# Sheet1.net
KiCad netlist of a schematic drawn in Altium Designer
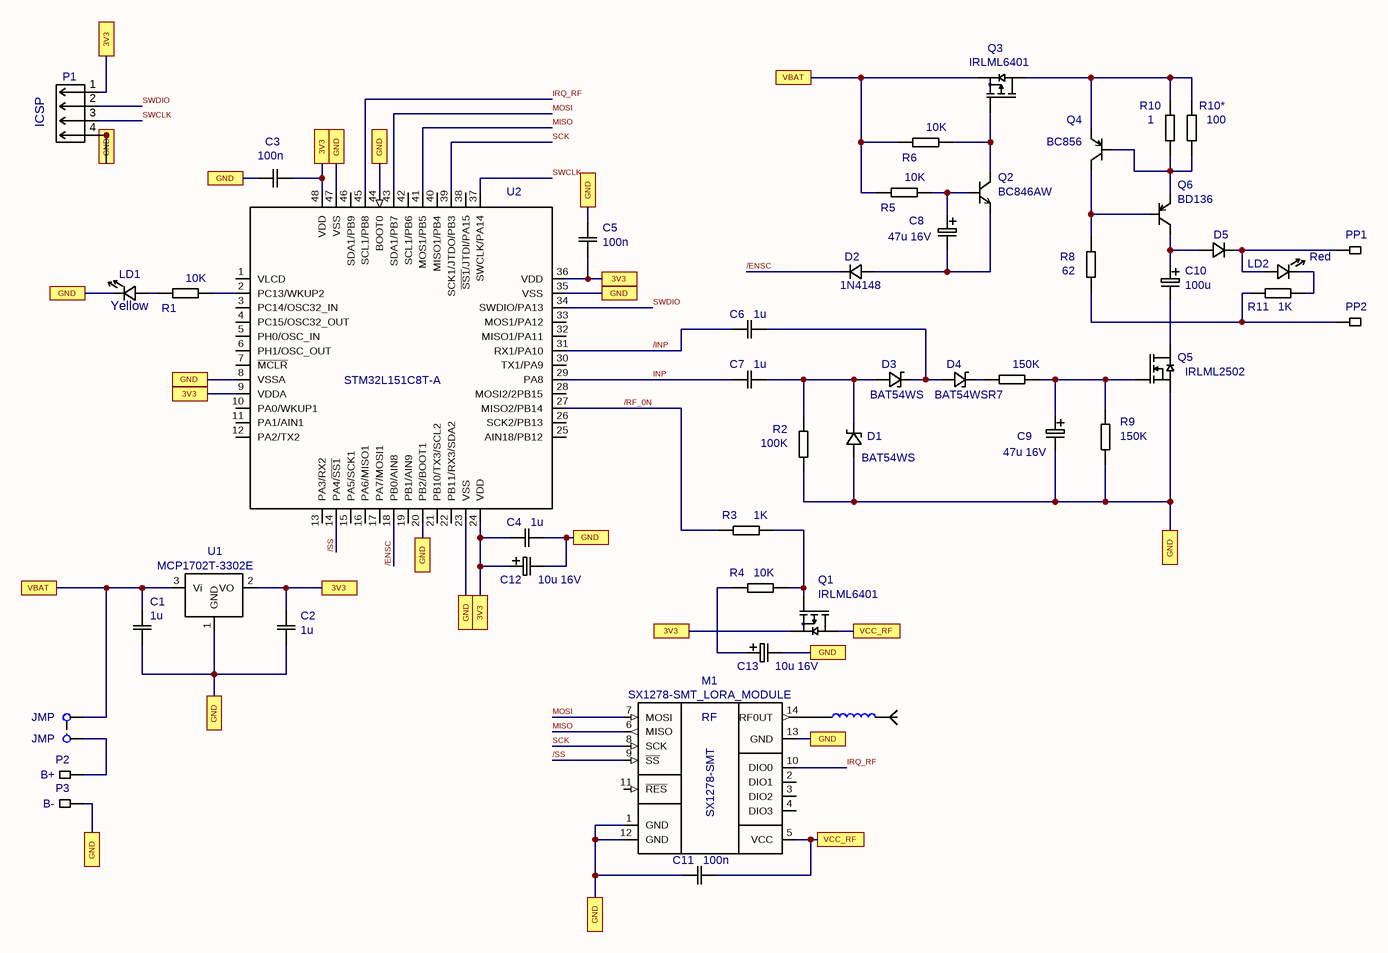
[diagram p0: Sheet1.SCHDOC]

(export (version "E")
  (design (tool "Eeschema 10.0.6"))
  (components
    (comp (ref "C1")
      (value "1u")
      (footprint "C0805")
      (description "CAP_SMD_0805")
      (libsource (lib "*") (part "CAP_SMD_0805"))
    )
    (comp (ref "C2")
      (value "1u")
      (footprint "C0805")
      (description "CAP_SMD_0805")
      (libsource (lib "*") (part "CAP_SMD_0805"))
    )
    (comp (ref "C3")
      (value "100n")
      (footprint "C0805")
      (description "CAP_SMD_0805")
      (libsource (lib "") (part "CAP_SMD_0805_1"))
    )
    (comp (ref "C4")
      (value "1u")
      (footprint "C0805")
      (description "CAP_SMD_0805")
      (libsource (lib "") (part "CAP_SMD_0805_1"))
    )
    (comp (ref "C5")
      (value "100n")
      (footprint "C0805")
      (description "CAP_SMD_0805")
      (libsource (lib "*") (part "CAP_SMD_0805"))
    )
    (comp (ref "C6")
      (value "1u")
      (footprint "C0805")
      (description "CAP_SMD_0805")
      (libsource (lib "") (part "CAP_SMD_0805_1"))
    )
    (comp (ref "C7")
      (value "1u")
      (footprint "C0805")
      (description "CAP_SMD_0805")
      (libsource (lib "") (part "CAP_SMD_0805_2"))
    )
    (comp (ref "C8")
      (value "47u 16V")
      (footprint "ECAP-SD-D5L11")
      (description "ECAP-RD-D5L11")
      (libsource (lib "*") (part "ECAP-RD-D5L11"))
    )
    (comp (ref "C9")
      (value "47u 16V")
      (footprint "ECAP-SD-D5L11")
      (description "ECAP-RD-D5L11")
      (libsource (lib "*") (part "ECAP-RD-D5L11"))
    )
    (comp (ref "C10")
      (value "100u")
      (footprint "ECAP-SD-D6.3L11")
      (description "ECAP-RD-D6.3L11")
      (libsource (lib "*") (part "ECAP-RD-D6.3L11"))
    )
    (comp (ref "C11")
      (value "100n")
      (footprint "C0805")
      (description "CAP_SMD_0805")
      (libsource (lib "") (part "CAP_SMD_0805_2"))
    )
    (comp (ref "C12")
      (value "10u 16V")
      (footprint "ECAP-SD-D5L11")
      (description "ECAP-RD-D5L11")
      (libsource (lib "*") (part "ECAP-RD-D5L11"))
    )
    (comp (ref "C13")
      (value "10u 16V")
      (footprint "ECAP-SD-D5L11")
      (description "ECAP-RD-D5L11")
      (libsource (lib "*") (part "ECAP-RD-D5L11"))
    )
    (comp (ref "D1") (value "BAT54WS") (footprint "SOD323") (libsource (lib "*") (part "BAT54WS")))
    (comp (ref "D2") (value "1N4148") (footprint "SOD80") (libsource (lib "*") (part "1N4148")))
    (comp (ref "D3") (value "BAT54WS") (footprint "SOD323") (libsource (lib "*") (part "BAT54WS")))
    (comp (ref "D4") (value "BAT54WS") (footprint "SOD323") (libsource (lib "*") (part "BAT54WS")))
    (comp (ref "D5") (value "1N4007-A7") (footprint "SOD-123FL") (libsource (lib "*") (part "1N4007-A7")))
    (comp (ref "LD1")
      (value "Yellow")
      (footprint "LED_SMD_0805")
      (description "Yellow LED. 2.6Vf")
      (fields (field (name "Comment") "FYLS-0805BYC LED"))
      (libsource (lib "*") (part "FYLS-0805BYC LED"))
    )
    (comp (ref "LD2")
      (value "Red")
      (footprint "LED_SMD_0805")
      (description "Ultra Red. Vf-1.85V(2.2V max)")
      (fields (field (name "Comment") "FYLS-0805URC LED"))
      (libsource (lib "*") (part "FYLS-0805URC LED"))
    )
    (comp (ref "M1")
      (value "SX1278-SMT_LORA_MODULE")
      (footprint "SX1278-SMT_MODULE")
      (libsource (lib "*") (part "SX1278-SMT_LORA_MODULE"))
    )
    (comp (ref "P1")
      (value "ICSP")
      (footprint "PLS-04SMD")
      (description "PLS-04SMD")
      (libsource (lib "*") (part "PLS-04SMD"))
    )
    (comp (ref "P2")
      (value "B+")
      (footprint "PAD_RRX60Y120D0T")
      (description "PAD_RRX60Y120D0T")
      (libsource (lib "*") (part "PAD_RRX60Y120D0T"))
    )
    (comp (ref "P3")
      (value "B-")
      (footprint "PAD_RRX60Y120D0T")
      (description "PAD_RRX60Y120D0T")
      (libsource (lib "*") (part "PAD_RRX60Y120D0T"))
    )
    (comp (ref "PP1")
      (value "PAD_RRX60Y120D0T")
      (footprint "PAD_RRX60Y120D0T")
      (libsource (lib "*") (part "PAD_RRX60Y120D0T"))
    )
    (comp (ref "PP2")
      (value "PAD_RRX60Y120D0T")
      (footprint "PAD_RRX60Y120D0T")
      (libsource (lib "*") (part "PAD_RRX60Y120D0T"))
    )
    (comp (ref "PP3")
      (value "JMP")
      (footprint "PAD_RX60Y60D38A")
      (description "PAD_RX60Y60D38A")
      (libsource (lib "*") (part "PAD_RX60Y60D38A"))
    )
    (comp (ref "PP4")
      (value "JMP")
      (footprint "PAD_RX60Y60D38A")
      (description "PAD_RX60Y60D38A")
      (libsource (lib "*") (part "PAD_RX60Y60D38A"))
    )
    (comp (ref "Q1") (value "IRLML6401") (footprint "SOT23") (libsource (lib "*") (part "IRLML6401")))
    (comp (ref "Q2") (value "BC846AW") (footprint "SOT23") (libsource (lib "*") (part "BC846AW")))
    (comp (ref "Q3") (value "IRLML6401") (footprint "SOT23") (libsource (lib "") (part "IRLML6401_1")))
    (comp (ref "Q4") (value "BC856") (footprint "SOT23") (libsource (lib "*") (part "BC856")))
    (comp (ref "Q5") (value "IRLML2502") (footprint "SOT23") (libsource (lib "*") (part "IRLML2502")))
    (comp (ref "Q6") (value "BD136") (footprint "TO225 VH") (libsource (lib "*") (part "BD136")))
    (comp (ref "R1")
      (value "10K")
      (footprint "R0805")
      (description "RES_SMD_0805")
      (libsource (lib "*") (part "RES_SMD_0805"))
    )
    (comp (ref "R2")
      (value "100K")
      (footprint "R0805")
      (description "RES_SMD_0805")
      (libsource (lib "*") (part "RES_SMD_0805"))
    )
    (comp (ref "R3")
      (value "1K")
      (footprint "R0805")
      (description "RES_SMD_0805")
      (libsource (lib "*") (part "RES_SMD_0805"))
    )
    (comp (ref "R4")
      (value "10K")
      (footprint "R0805")
      (description "RES_SMD_0805")
      (libsource (lib "*") (part "RES_SMD_0805"))
    )
    (comp (ref "R5")
      (value "10K")
      (footprint "R0805")
      (description "RES_SMD_0805")
      (libsource (lib "*") (part "RES_SMD_0805"))
    )
    (comp (ref "R6")
      (value "10K")
      (footprint "R0805")
      (description "RES_SMD_0805")
      (libsource (lib "*") (part "RES_SMD_0805"))
    )
    (comp (ref "R7")
      (value "150K")
      (footprint "R0805")
      (description "RES_SMD_0805")
      (libsource (lib "*") (part "RES_SMD_0805"))
    )
    (comp (ref "R8")
      (value "62")
      (footprint "R0805")
      (description "RES_SMD_0805")
      (libsource (lib "*") (part "RES_SMD_0805"))
    )
    (comp (ref "R9")
      (value "150K")
      (footprint "R0805")
      (description "RES_SMD_0805")
      (libsource (lib "*") (part "RES_SMD_0805"))
    )
    (comp (ref "R10")
      (value "1")
      (footprint "R0805")
      (description "RES_SMD_0805")
      (libsource (lib "*") (part "RES_SMD_0805"))
    )
    (comp (ref "R10*")
      (value "100")
      (footprint "R0805")
      (description "RES_SMD_0805")
      (libsource (lib "*") (part "RES_SMD_0805"))
    )
    (comp (ref "R11")
      (value "1K")
      (footprint "R0805")
      (description "RES_SMD_0805")
      (libsource (lib "*") (part "RES_SMD_0805"))
    )
    (comp (ref "U1")
      (value "MCP1702T-3302E")
      (footprint "SOT23A")
      (libsource (lib "*") (part "MCP1702T-3302E"))
    )
    (comp (ref "U2")
      (value "STM32L151C8T-A")
      (footprint "LQFP48 7X7")
      (libsource (lib "*") (part "STM32L151C8T-A"))
    )
  )
  (nets
    (net (code "1") (name "/3V3") (class "Default")
      (node (ref "C12") (pin "1") (pintype "passive"))
      (node (ref "C2") (pin "2") (pinfunction "B_2") (pintype "passive"))
      (node (ref "C3") (pin "1") (pinfunction "A_1") (pintype "passive"))
      (node (ref "C4") (pin "2") (pinfunction "B_2") (pintype "passive"))
      (node (ref "C5") (pin "1") (pinfunction "A_1") (pintype "passive"))
      (node (ref "P1") (pin "1") (pintype "passive"))
      (node (ref "Q1") (pin "2") (pinfunction "S_2") (pintype "passive"))
      (node (ref "U1") (pin "2") (pinfunction "VO_2") (pintype "passive"))
      (node (ref "U2") (pin "24") (pinfunction "VDD_24") (pintype "power_in"))
      (node (ref "U2") (pin "36") (pinfunction "VDD_36") (pintype "power_in"))
      (node (ref "U2") (pin "48") (pinfunction "VDD_48") (pintype "power_in"))
      (node (ref "U2") (pin "9") (pinfunction "VDDA_9") (pintype "power_in"))
    )
    (net (code "2") (name "/GND") (class "Default")
      (node (ref "C1") (pin "1") (pinfunction "A_1") (pintype "passive"))
      (node (ref "C11") (pin "1") (pinfunction "A_1") (pintype "passive"))
      (node (ref "C12") (pin "2") (pintype "passive"))
      (node (ref "C13") (pin "2") (pintype "passive"))
      (node (ref "C2") (pin "1") (pinfunction "A_1") (pintype "passive"))
      (node (ref "C3") (pin "2") (pinfunction "B_2") (pintype "passive"))
      (node (ref "C4") (pin "1") (pinfunction "A_1") (pintype "passive"))
      (node (ref "C5") (pin "2") (pinfunction "B_2") (pintype "passive"))
      (node (ref "C9") (pin "2") (pintype "passive"))
      (node (ref "D1") (pin "1") (pintype "passive"))
      (node (ref "LD1") (pin "K") (pinfunction "K_K") (pintype "passive"))
      (node (ref "M1") (pin "1") (pinfunction "GND_1") (pintype "power_in"))
      (node (ref "M1") (pin "12") (pinfunction "GND_12") (pintype "power_in"))
      (node (ref "M1") (pin "13") (pinfunction "GND_13") (pintype "power_in"))
      (node (ref "P1") (pin "4") (pintype "passive"))
      (node (ref "P3") (pin "1") (pintype "passive"))
      (node (ref "Q5") (pin "2") (pinfunction "S_2") (pintype "passive"))
      (node (ref "R2") (pin "2") (pintype "passive"))
      (node (ref "R9") (pin "2") (pintype "passive"))
      (node (ref "U1") (pin "1") (pinfunction "GND_1") (pintype "passive"))
      (node (ref "U2") (pin "20") (pinfunction "PB2/BOOT1_20") (pintype "bidirectional"))
      (node (ref "U2") (pin "23") (pinfunction "VSS_23") (pintype "power_in"))
      (node (ref "U2") (pin "35") (pinfunction "VSS_35") (pintype "power_in"))
      (node (ref "U2") (pin "44") (pinfunction "BOOT0_44") (pintype "input"))
      (node (ref "U2") (pin "47") (pinfunction "VSS_47") (pintype "power_in"))
      (node (ref "U2") (pin "8") (pinfunction "VSSA_8") (pintype "power_in"))
    )
    (net (code "3") (name "/INP") (class "Default")
      (node (ref "C7") (pin "1") (pinfunction "A_1") (pintype "passive"))
      (node (ref "U2") (pin "29") (pinfunction "PA8_29") (pintype "bidirectional"))
    )
    (net (code "4") (name "/IRQ_RF") (class "Default")
      (node (ref "M1") (pin "10") (pinfunction "DIO0_10") (pintype "bidirectional"))
      (node (ref "U2") (pin "45") (pinfunction "SCL1/PB8_45") (pintype "bidirectional"))
    )
    (net (code "5") (name "/MISO") (class "Default")
      (node (ref "M1") (pin "6") (pinfunction "MISO_6") (pintype "output"))
      (node (ref "U2") (pin "41") (pinfunction "MOS1/PB5_41") (pintype "bidirectional"))
    )
    (net (code "6") (name "/MOSI") (class "Default")
      (node (ref "M1") (pin "7") (pinfunction "MOSI_7") (pintype "input"))
      (node (ref "U2") (pin "43") (pinfunction "SDA1/PB7_43") (pintype "bidirectional"))
    )
    (net (code "7") (name "/SCK") (class "Default")
      (node (ref "M1") (pin "8") (pinfunction "SCK_8") (pintype "input"))
      (node (ref "U2") (pin "39") (pinfunction "SCK1/JTDO/PB3_39") (pintype "bidirectional"))
    )
    (net (code "8") (name "/SWCLK") (class "Default")
      (node (ref "P1") (pin "3") (pintype "passive"))
      (node (ref "U2") (pin "37") (pinfunction "SWCLK/PA14_37") (pintype "bidirectional"))
    )
    (net (code "9") (name "/SWDIO") (class "Default")
      (node (ref "P1") (pin "2") (pintype "passive"))
      (node (ref "U2") (pin "34") (pinfunction "SWDIO/PA13_34") (pintype "bidirectional"))
    )
    (net (code "10") (name "/VBAT") (class "Default")
      (node (ref "C1") (pin "2") (pinfunction "B_2") (pintype "passive"))
      (node (ref "PP4") (pin "1") (pintype "passive"))
      (node (ref "Q3") (pin "2") (pinfunction "S_2") (pintype "passive"))
      (node (ref "R5") (pin "2") (pintype "passive"))
      (node (ref "R6") (pin "2") (pintype "passive"))
      (node (ref "U1") (pin "3") (pinfunction "Vi_3") (pintype "passive"))
    )
    (net (code "11") (name "/VCC_RF") (class "Default")
      (node (ref "C11") (pin "2") (pinfunction "B_2") (pintype "passive"))
      (node (ref "M1") (pin "5") (pinfunction "VCC_5") (pintype "power_in"))
      (node (ref "Q1") (pin "3") (pinfunction "D_3") (pintype "passive"))
    )
    (net (code "12") (name "/{slash}ENSC") (class "Default")
      (node (ref "D2") (pin "K") (pinfunction "K_K") (pintype "passive"))
      (node (ref "U2") (pin "18") (pinfunction "PB0/AIN8_18") (pintype "bidirectional"))
    )
    (net (code "13") (name "/{slash}INP") (class "Default")
      (node (ref "C6") (pin "2") (pinfunction "B_2") (pintype "passive"))
      (node (ref "U2") (pin "31") (pinfunction "RX1/PA10_31") (pintype "bidirectional"))
    )
    (net (code "14") (name "/{slash}RF_0N") (class "Default")
      (node (ref "R3") (pin "2") (pintype "passive"))
      (node (ref "U2") (pin "27") (pinfunction "MISO2/PB14_27") (pintype "bidirectional"))
    )
    (net (code "15") (name "/{slash}SS") (class "Default")
      (node (ref "M1") (pin "9") (pinfunction "~{SS}_9") (pintype "input"))
      (node (ref "U2") (pin "14") (pinfunction "PA4/~{SS1}_14") (pintype "bidirectional"))
    )
    (net (code "16") (name "Net-(C6-A)") (class "Default")
      (node (ref "C6") (pin "1") (pinfunction "A_1") (pintype "passive"))
      (node (ref "D3") (pin "2") (pintype "passive"))
      (node (ref "D4") (pin "1") (pintype "passive"))
    )
    (net (code "17") (name "Net-(C7-B)") (class "Default")
      (node (ref "C7") (pin "2") (pinfunction "B_2") (pintype "passive"))
      (node (ref "D1") (pin "2") (pintype "passive"))
      (node (ref "D3") (pin "1") (pintype "passive"))
      (node (ref "R2") (pin "1") (pintype "passive"))
    )
    (net (code "18") (name "Net-(C13-Pad1)") (class "Default")
      (node (ref "C13") (pin "1") (pintype "passive"))
      (node (ref "R4") (pin "2") (pintype "passive"))
    )
    (net (code "19") (name "Net-(D4-Pad2)") (class "Default")
      (node (ref "D4") (pin "2") (pintype "passive"))
      (node (ref "R7") (pin "2") (pintype "passive"))
    )
    (net (code "20") (name "Net-(D5-A)") (class "Default")
      (node (ref "C10") (pin "1") (pintype "passive"))
      (node (ref "D5") (pin "1") (pinfunction "A_1") (pintype "passive"))
      (node (ref "Q6") (pin "2") (pinfunction "K_2") (pintype "passive"))
    )
    (net (code "21") (name "Net-(D5-K)") (class "Default")
      (node (ref "D5") (pin "2") (pinfunction "K_2") (pintype "passive"))
      (node (ref "LD2") (pin "A") (pinfunction "A_A") (pintype "passive"))
      (node (ref "PP1") (pin "1") (pintype "passive"))
    )
    (net (code "22") (name "Net-(LD1-PadA)") (class "Default")
      (node (ref "LD1") (pin "A") (pinfunction "A_A") (pintype "passive"))
      (node (ref "R1") (pin "2") (pintype "passive"))
    )
    (net (code "23") (name "Net-(LD2-PadK)") (class "Default")
      (node (ref "LD2") (pin "K") (pinfunction "K_K") (pintype "passive"))
      (node (ref "R11") (pin "1") (pintype "passive"))
    )
    (net (code "24") (name "Net-(P2-Pad1)") (class "Default")
      (node (ref "P2") (pin "1") (pintype "passive"))
      (node (ref "PP3") (pin "1") (pintype "passive"))
    )
    (net (code "25") (name "Net-(PP2-Pad1)") (class "Default")
      (node (ref "PP2") (pin "1") (pintype "passive"))
      (node (ref "R11") (pin "2") (pintype "passive"))
      (node (ref "R8") (pin "2") (pintype "passive"))
    )
    (net (code "26") (name "Net-(Q1-G)") (class "Default")
      (node (ref "Q1") (pin "1") (pinfunction "G_1") (pintype "passive"))
      (node (ref "R3") (pin "1") (pintype "passive"))
      (node (ref "R4") (pin "1") (pintype "passive"))
    )
    (net (code "27") (name "Net-(Q2-B)") (class "Default")
      (node (ref "C8") (pin "1") (pintype "passive"))
      (node (ref "Q2") (pin "1") (pinfunction "B_1") (pintype "passive"))
      (node (ref "R5") (pin "1") (pintype "passive"))
    )
    (net (code "28") (name "Net-(Q2-C)") (class "Default")
      (node (ref "Q2") (pin "3") (pinfunction "C_3") (pintype "passive"))
      (node (ref "Q3") (pin "1") (pinfunction "G_1") (pintype "passive"))
      (node (ref "R6") (pin "1") (pintype "passive"))
    )
    (net (code "29") (name "Net-(Q2-E)") (class "Default")
      (node (ref "C8") (pin "2") (pintype "passive"))
      (node (ref "D2") (pin "A") (pinfunction "A_A") (pintype "passive"))
      (node (ref "Q2") (pin "2") (pinfunction "E_2") (pintype "passive"))
    )
    (net (code "30") (name "Net-(Q3-D)") (class "Default")
      (node (ref "Q3") (pin "3") (pinfunction "D_3") (pintype "passive"))
      (node (ref "Q4") (pin "2") (pinfunction "E_2") (pintype "passive"))
      (node (ref "R10") (pin "1") (pintype "passive"))
      (node (ref "R10*") (pin "1") (pintype "passive"))
    )
    (net (code "31") (name "Net-(Q4-B)") (class "Default")
      (node (ref "Q4") (pin "1") (pinfunction "B_1") (pintype "passive"))
      (node (ref "Q6") (pin "1") (pinfunction "E_1") (pintype "passive"))
      (node (ref "R10") (pin "2") (pintype "passive"))
      (node (ref "R10*") (pin "2") (pintype "passive"))
    )
    (net (code "32") (name "Net-(Q4-C)") (class "Default")
      (node (ref "Q4") (pin "3") (pinfunction "C_3") (pintype "passive"))
      (node (ref "Q6") (pin "3") (pinfunction "B_3") (pintype "passive"))
      (node (ref "R8") (pin "1") (pintype "passive"))
    )
    (net (code "33") (name "Net-(Q5-D)") (class "Default")
      (node (ref "C10") (pin "2") (pintype "passive"))
      (node (ref "Q5") (pin "3") (pinfunction "D_3") (pintype "passive"))
    )
    (net (code "34") (name "Net-(Q5-G)") (class "Default")
      (node (ref "C9") (pin "1") (pintype "passive"))
      (node (ref "Q5") (pin "1") (pinfunction "G_1") (pintype "passive"))
      (node (ref "R7") (pin "1") (pintype "passive"))
      (node (ref "R9") (pin "1") (pintype "passive"))
    )
    (net (code "35") (name "Net-(U2-PC13{slash}WKUP2)") (class "Default")
      (node (ref "R1") (pin "1") (pintype "passive"))
      (node (ref "U2") (pin "2") (pinfunction "PC13/WKUP2_2") (pintype "bidirectional"))
    )
    (net (code "36") (name "unconnected-(M1-DIO1-Pad2)") (class "Default")
      (node (ref "M1") (pin "2") (pinfunction "DIO1_2") (pintype "bidirectional"))
    )
    (net (code "37") (name "unconnected-(M1-DIO2-Pad3)") (class "Default")
      (node (ref "M1") (pin "3") (pinfunction "DIO2_3") (pintype "bidirectional"))
    )
    (net (code "38") (name "unconnected-(M1-DIO3-Pad4)") (class "Default")
      (node (ref "M1") (pin "4") (pinfunction "DIO3_4") (pintype "bidirectional"))
    )
    (net (code "39") (name "unconnected-(M1-RF0UT-Pad14)") (class "Default")
      (node (ref "M1") (pin "14") (pinfunction "RF0UT_14") (pintype "output"))
    )
    (net (code "40") (name "unconnected-(M1-~{RES}-Pad11)") (class "Default")
      (node (ref "M1") (pin "11") (pinfunction "~{RES}_11") (pintype "input"))
    )
    (net (code "41") (name "unconnected-(U2-AIN18{slash}PB12-Pad25)") (class "Default")
      (node (ref "U2") (pin "25") (pinfunction "AIN18/PB12_25") (pintype "bidirectional"))
    )
    (net (code "42") (name "unconnected-(U2-MISO1{slash}PA11-Pad32)") (class "Default")
      (node (ref "U2") (pin "32") (pinfunction "MISO1/PA11_32") (pintype "bidirectional"))
    )
    (net (code "43") (name "unconnected-(U2-MISO1{slash}PB4-Pad40)") (class "Default")
      (node (ref "U2") (pin "40") (pinfunction "MISO1/PB4_40") (pintype "bidirectional"))
    )
    (net (code "44") (name "unconnected-(U2-MOS1{slash}PA12-Pad33)") (class "Default")
      (node (ref "U2") (pin "33") (pinfunction "MOS1/PA12_33") (pintype "bidirectional"))
    )
    (net (code "45") (name "unconnected-(U2-MOSI2{slash}2PB15-Pad28)") (class "Default")
      (node (ref "U2") (pin "28") (pinfunction "MOSI2/2PB15_28") (pintype "bidirectional"))
    )
    (net (code "46") (name "unconnected-(U2-PA0{slash}WKUP1-Pad10)") (class "Default")
      (node (ref "U2") (pin "10") (pinfunction "PA0/WKUP1_10") (pintype "bidirectional"))
    )
    (net (code "47") (name "unconnected-(U2-PA1{slash}AIN1-Pad11)") (class "Default")
      (node (ref "U2") (pin "11") (pinfunction "PA1/AIN1_11") (pintype "bidirectional"))
    )
    (net (code "48") (name "unconnected-(U2-PA2{slash}TX2-Pad12)") (class "Default")
      (node (ref "U2") (pin "12") (pinfunction "PA2/TX2_12") (pintype "bidirectional"))
    )
    (net (code "49") (name "unconnected-(U2-PA3{slash}RX2-Pad13)") (class "Default")
      (node (ref "U2") (pin "13") (pinfunction "PA3/RX2_13") (pintype "bidirectional"))
    )
    (net (code "50") (name "unconnected-(U2-PA5{slash}SCK1-Pad15)") (class "Default")
      (node (ref "U2") (pin "15") (pinfunction "PA5/SCK1_15") (pintype "bidirectional"))
    )
    (net (code "51") (name "unconnected-(U2-PA6{slash}MISO1-Pad16)") (class "Default")
      (node (ref "U2") (pin "16") (pinfunction "PA6/MISO1_16") (pintype "bidirectional"))
    )
    (net (code "52") (name "unconnected-(U2-PA7{slash}MOSI1-Pad17)") (class "Default")
      (node (ref "U2") (pin "17") (pinfunction "PA7/MOSI1_17") (pintype "bidirectional"))
    )
    (net (code "53") (name "unconnected-(U2-PB1{slash}AIN9-Pad19)") (class "Default")
      (node (ref "U2") (pin "19") (pinfunction "PB1/AIN9_19") (pintype "bidirectional"))
    )
    (net (code "54") (name "unconnected-(U2-PB10{slash}TX3{slash}SCL2-Pad21)") (class "Default")
      (node (ref "U2") (pin "21") (pinfunction "PB10/TX3/SCL2_21") (pintype "bidirectional"))
    )
    (net (code "55") (name "unconnected-(U2-PB11{slash}RX3{slash}SDA2-Pad22)") (class "Default")
      (node (ref "U2") (pin "22") (pinfunction "PB11/RX3/SDA2_22") (pintype "bidirectional"))
    )
    (net (code "56") (name "unconnected-(U2-PC14{slash}OSC32_IN-Pad3)") (class "Default")
      (node (ref "U2") (pin "3") (pinfunction "PC14/OSC32_IN_3") (pintype "bidirectional"))
    )
    (net (code "57") (name "unconnected-(U2-PC15{slash}OSC32_OUT-Pad4)") (class "Default")
      (node (ref "U2") (pin "4") (pinfunction "PC15/OSC32_OUT_4") (pintype "bidirectional"))
    )
    (net (code "58") (name "unconnected-(U2-PH0{slash}OSC_IN-Pad5)") (class "Default")
      (node (ref "U2") (pin "5") (pinfunction "PH0/OSC_IN_5") (pintype "bidirectional"))
    )
    (net (code "59") (name "unconnected-(U2-PH1{slash}OSC_OUT-Pad6)") (class "Default")
      (node (ref "U2") (pin "6") (pinfunction "PH1/OSC_OUT_6") (pintype "bidirectional"))
    )
    (net (code "60") (name "unconnected-(U2-SCK2{slash}PB13-Pad26)") (class "Default")
      (node (ref "U2") (pin "26") (pinfunction "SCK2/PB13_26") (pintype "bidirectional"))
    )
    (net (code "61") (name "unconnected-(U2-SCL1{slash}PB6-Pad42)") (class "Default")
      (node (ref "U2") (pin "42") (pinfunction "SCL1/PB6_42") (pintype "bidirectional"))
    )
    (net (code "62") (name "unconnected-(U2-SDA1{slash}PB9-Pad46)") (class "Default")
      (node (ref "U2") (pin "46") (pinfunction "SDA1/PB9_46") (pintype "bidirectional"))
    )
    (net (code "63") (name "unconnected-(U2-TX1{slash}PA9-Pad30)") (class "Default")
      (node (ref "U2") (pin "30") (pinfunction "TX1/PA9_30") (pintype "bidirectional"))
    )
    (net (code "64") (name "unconnected-(U2-VLCD-Pad1)") (class "Default")
      (node (ref "U2") (pin "1") (pinfunction "VLCD_1") (pintype "power_in"))
    )
    (net (code "65") (name "unconnected-(U2-~{MCLR}-Pad7)") (class "Default")
      (node (ref "U2") (pin "7") (pinfunction "~{MCLR}_7") (pintype "bidirectional"))
    )
    (net (code "66") (name "unconnected-(U2-~{SS1}{slash}JTDI{slash}PA15-Pad38)") (class "Default")
      (node (ref "U2") (pin "38") (pinfunction "~{SS1}/JTDI/PA15_38") (pintype "bidirectional"))
    )
  )
)
